# CH32V467WEU-R0.net
KiCad netlist of a schematic drawn in Altium Designer
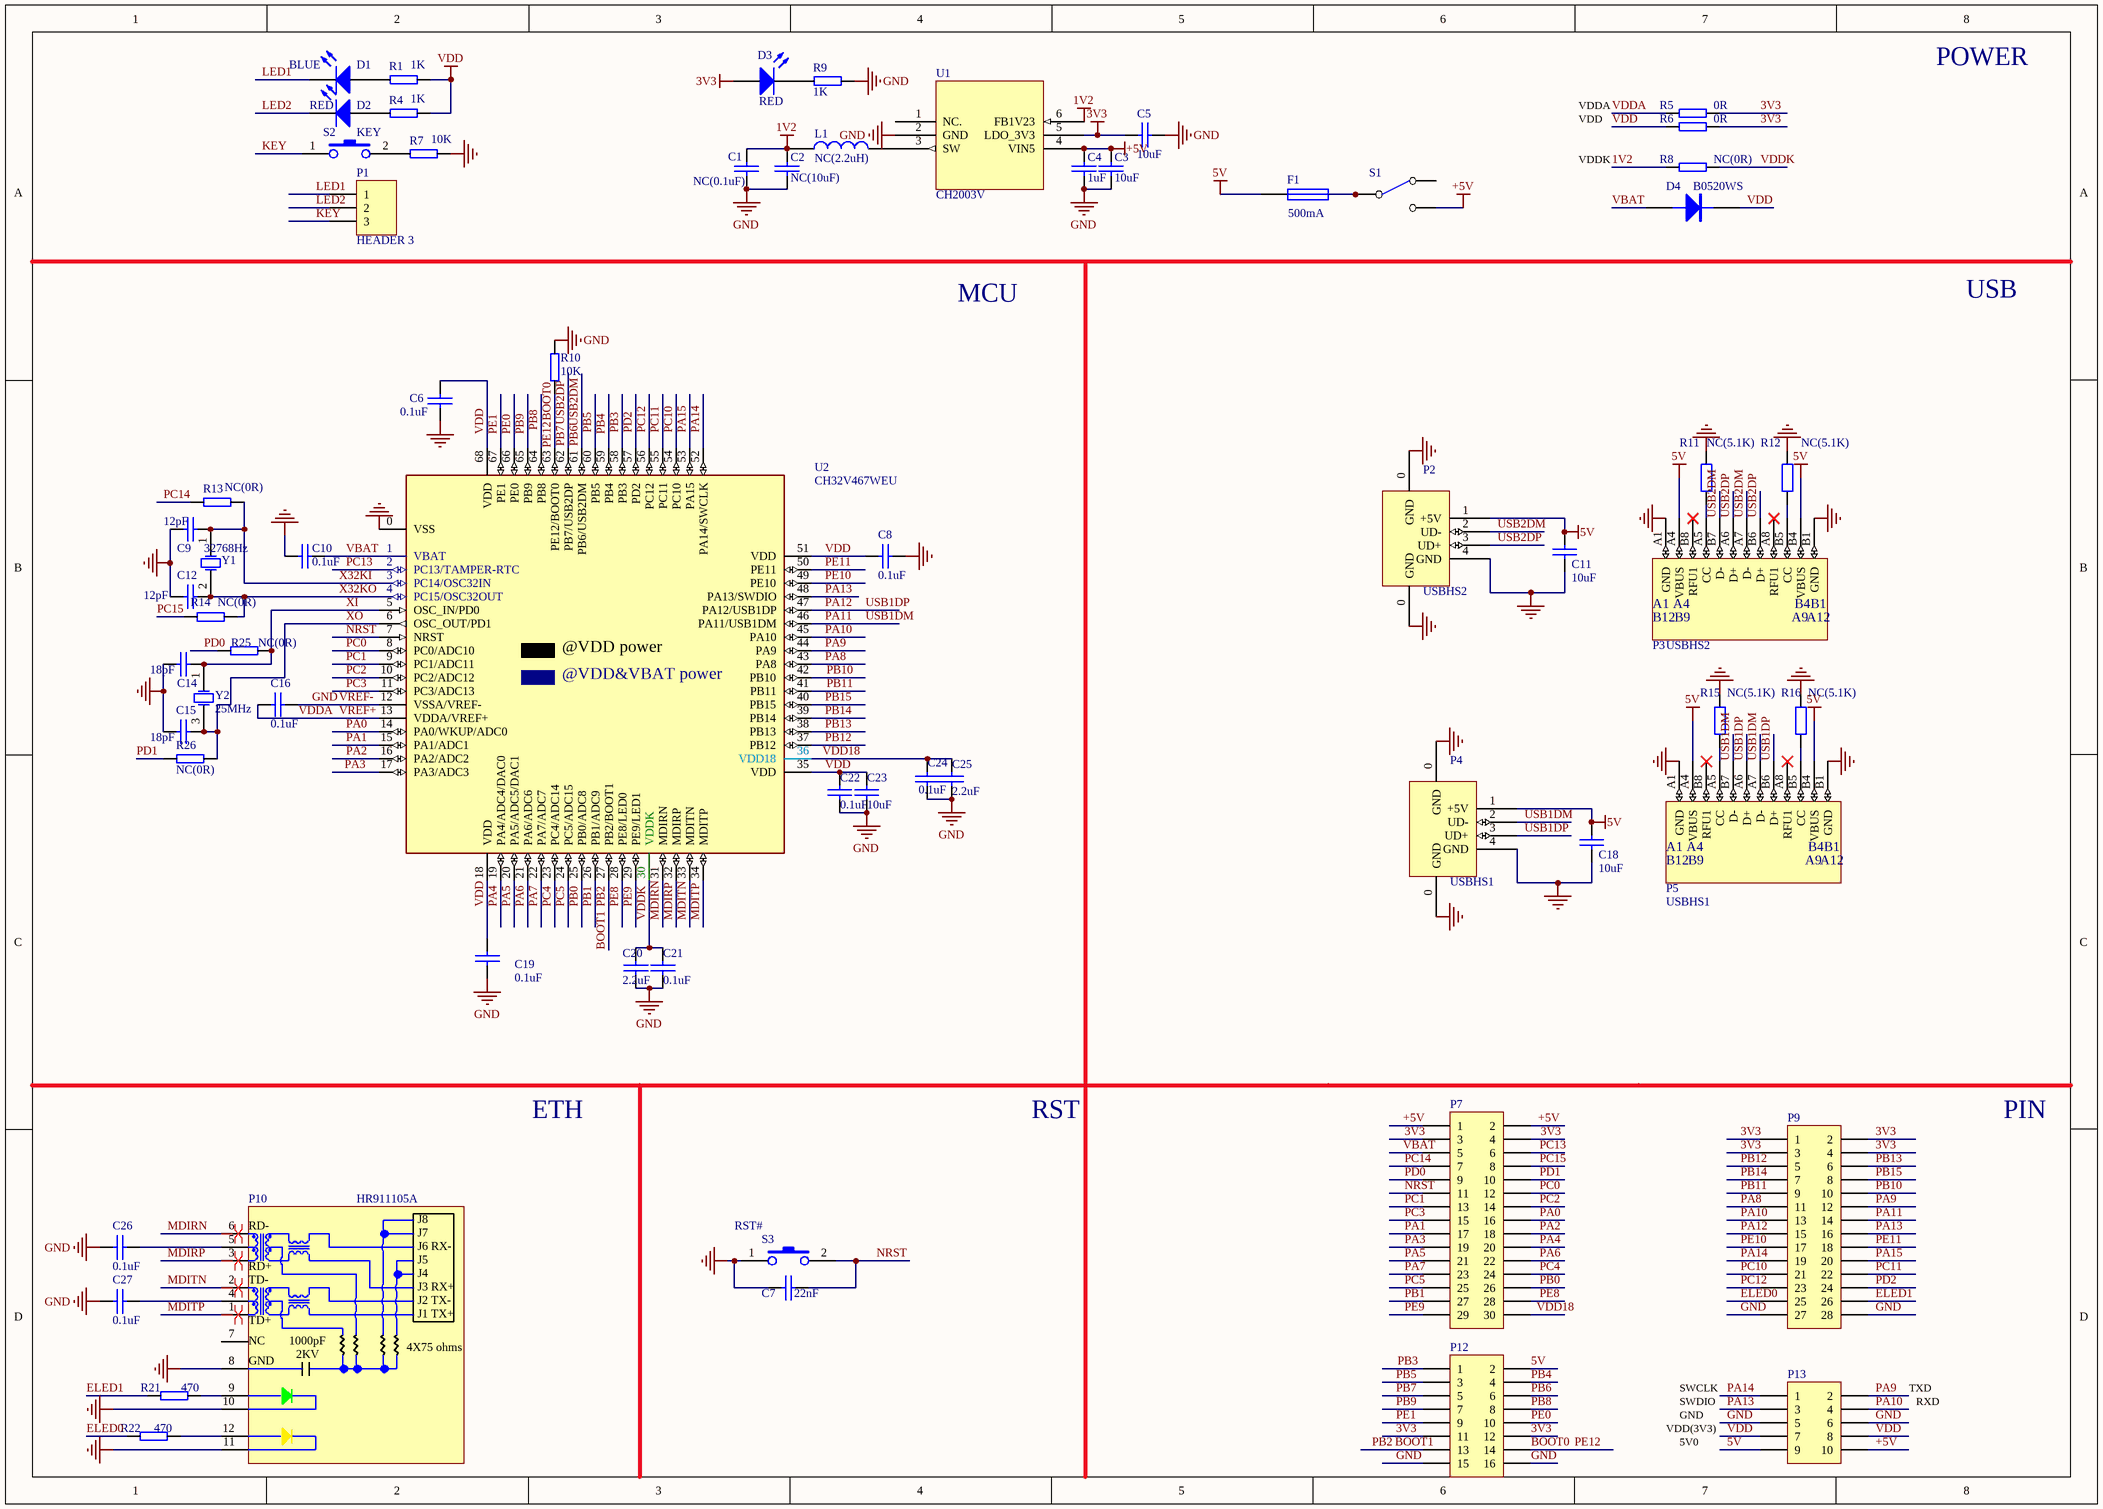
[diagram p0: CH32V467WEU-R0.SchDoc]

(export (version "E")
  (design (tool "Eeschema 10.0.6"))
  (components
    (comp (ref "C1")
      (value "NC(0.1uF)")
      (footprint "0402_C")
      (description "Capacitor")
      (libsource (lib "") (part "CAP_2"))
    )
    (comp (ref "C2")
      (value "NC(10uF)")
      (footprint "0603_C")
      (description "Capacitor")
      (libsource (lib "*") (part "CAP"))
    )
    (comp (ref "C3")
      (value "10uF")
      (footprint "0603_C")
      (description "Capacitor")
      (libsource (lib "*") (part "CAP"))
    )
    (comp (ref "C4")
      (value "1uF")
      (footprint "0402_C")
      (description "Capacitor")
      (libsource (lib "") (part "CAP_2"))
    )
    (comp (ref "C5")
      (value "10uF")
      (footprint "0603_C")
      (description "Capacitor")
      (libsource (lib "*") (part "CAP"))
    )
    (comp (ref "C6")
      (value "0.1uF")
      (footprint "0402_C")
      (description "Capacitor")
      (libsource (lib "*") (part "CAP"))
    )
    (comp (ref "C7")
      (value "22nF")
      (footprint "0402_C")
      (description "Capacitor")
      (libsource (lib "") (part "CAP_1"))
    )
    (comp (ref "C8")
      (value "0.1uF")
      (footprint "0402_C")
      (description "Capacitor")
      (libsource (lib "*") (part "CAP"))
    )
    (comp (ref "C9")
      (value "12pF")
      (footprint "0402_C")
      (description "Capacitor")
      (libsource (lib "*") (part "CAP"))
    )
    (comp (ref "C10")
      (value "0.1uF")
      (footprint "0402_C")
      (description "Capacitor")
      (libsource (lib "*") (part "CAP"))
    )
    (comp (ref "C11")
      (value "10uF")
      (footprint "0603_C")
      (description "Capacitor")
      (libsource (lib "") (part "CAP_1"))
    )
    (comp (ref "C12")
      (value "12pF")
      (footprint "0402_C")
      (description "Capacitor")
      (libsource (lib "*") (part "CAP"))
    )
    (comp (ref "C14")
      (value "18pF")
      (footprint "0402_C")
      (description "Capacitor")
      (libsource (lib "*") (part "CAP"))
    )
    (comp (ref "C15")
      (value "18pF")
      (footprint "0402_C")
      (description "Capacitor")
      (libsource (lib "*") (part "CAP"))
    )
    (comp (ref "C16")
      (value "0.1uF")
      (footprint "0402_C")
      (description "Capacitor")
      (libsource (lib "*") (part "CAP"))
    )
    (comp (ref "C18")
      (value "10uF")
      (footprint "0603_C")
      (description "Capacitor")
      (libsource (lib "") (part "CAP_1"))
    )
    (comp (ref "C19")
      (value "0.1uF")
      (footprint "0402_C")
      (description "Capacitor")
      (libsource (lib "*") (part "CAP"))
    )
    (comp (ref "C20")
      (value "2.2uF")
      (footprint "0402_C")
      (description "Capacitor")
      (libsource (lib "*") (part "CAP"))
    )
    (comp (ref "C21")
      (value "0.1uF")
      (footprint "0402_C")
      (description "Capacitor")
      (libsource (lib "*") (part "CAP"))
    )
    (comp (ref "C22")
      (value "0.1uF")
      (footprint "0402_C")
      (description "Capacitor")
      (libsource (lib "*") (part "CAP"))
    )
    (comp (ref "C23")
      (value "10uF")
      (footprint "0603_C")
      (description "Capacitor")
      (libsource (lib "*") (part "CAP"))
    )
    (comp (ref "C24")
      (value "0.1uF")
      (footprint "0402_C")
      (description "Capacitor")
      (libsource (lib "*") (part "CAP"))
    )
    (comp (ref "C25")
      (value "2.2uF")
      (footprint "0402_C")
      (description "Capacitor")
      (libsource (lib "*") (part "CAP"))
    )
    (comp (ref "C26")
      (value "0.1uF")
      (footprint "0402_C")
      (description "Capacitor")
      (libsource (lib "wch_sch_others") (part "CAP"))
    )
    (comp (ref "C27")
      (value "0.1uF")
      (footprint "0402_C")
      (description "Capacitor")
      (libsource (lib "wch_sch_others") (part "CAP"))
    )
    (comp (ref "D1")
      (value "BLUE")
      (footprint "0603+")
      (description "Typical INFRARED GaAs LED")
      (fields (field (name "PUBLISHER") "Altium Limited"))
      (libsource (lib "*") (part "LED0"))
    )
    (comp (ref "D2")
      (value "RED")
      (footprint "0603+")
      (description "Typical INFRARED GaAs LED")
      (fields (field (name "PUBLISHER") "Altium Limited"))
      (libsource (lib "*") (part "LED0"))
    )
    (comp (ref "D3")
      (value "RED")
      (footprint "0603+")
      (description "Typical INFRARED GaAs LED")
      (fields (field (name "PUBLISHER") "Altium Limited"))
      (libsource (lib "*") (part "LED0"))
    )
    (comp (ref "D4")
      (value "B0520WS")
      (footprint "SOD-323")
      (description "Diode")
      (libsource (lib "*") (part "DIODE"))
    )
    (comp (ref "F1")
      (value "500mA")
      (footprint "0603")
      (description "Fuse")
      (libsource (lib "wch_sch_others") (part "FUSE1"))
    )
    (comp (ref "L1") (value "NC(2.2uH)") (footprint "CD32") (libsource (lib "*") (part "INDUCTOR")))
    (comp (ref "P1")
      (value "HEADER 3")
      (footprint "SIP3-2.54MM")
      (description "Header, 3-Pin")
      (libsource (lib "wch_sch_others") (part "HEADER 3"))
    )
    (comp (ref "P2")
      (value "USBHS2")
      (footprint "USBAF")
      (description "USB Port")
      (libsource (lib "*") (part "USB"))
    )
    (comp (ref "P3")
      (value "USBHS2")
      (footprint "TYPE-C-Receptacle-2.0")
      (libsource (lib "*") (part "TYPE-C1"))
    )
    (comp (ref "P4")
      (value "USBHS1")
      (footprint "USBAF")
      (description "USB Port")
      (libsource (lib "*") (part "USB"))
    )
    (comp (ref "P5")
      (value "USBHS1")
      (footprint "TYPE-C-Receptacle-2.0")
      (libsource (lib "*") (part "TYPE-C1"))
    )
    (comp (ref "P7")
      (value "HEADER 15x2")
      (footprint "MYPCB:IDC30-2.54MM")
      (description "Header, 15-Pin, Dual row")
      (libsource (lib "wch_sch_others") (part "HEADER 15x2"))
    )
    (comp (ref "P9")
      (value "HEADER 14x2")
      (footprint "MYPCB:IDC28-2.54MM")
      (description "Header, 14-Pin, Dual row")
      (libsource (lib "wch_sch_others") (part "HEADER 14x2"))
    )
    (comp (ref "P10") (value "HR911105A") (footprint "HR911105A") (libsource (lib "*") (part "HR911105A")))
    (comp (ref "P12")
      (value "Ppin")
      (footprint "IDC16-2.54mm")
      (description "Header, 8-Pin, Dual row, Right Angle")
      (fields (field (name "PUBLISHER") "Altium Limited"))
      (libsource (lib "Miscellaneous Connectors") (part "Header 8X2H"))
    )
    (comp (ref "P13")
      (value "LINK")
      (footprint "IDC10-2.54mm")
      (description "Header, 5-Pin, Dual row, Right Angle")
      (fields (field (name "PUBLISHER") "Altium Limited"))
      (libsource (lib "Miscellaneous Connectors") (part "Header 5X2H"))
    )
    (comp (ref "R1") (value "1K") (footprint "0402") (libsource (lib "wch_sch_others") (part "RES")))
    (comp (ref "R4") (value "1K") (footprint "0402") (libsource (lib "wch_sch_others") (part "RES")))
    (comp (ref "R5") (value "0R") (footprint "0402") (libsource (lib "*") (part "R")))
    (comp (ref "R6") (value "0R") (footprint "0402") (libsource (lib "*") (part "R")))
    (comp (ref "R7") (value "10K") (footprint "0402") (libsource (lib "wch_sch_others") (part "RES")))
    (comp (ref "R8") (value "NC(0R)") (footprint "0402") (libsource (lib "*") (part "R")))
    (comp (ref "R9") (value "1K") (footprint "0402") (libsource (lib "wch_sch_others") (part "RES")))
    (comp (ref "R10") (value "10K") (footprint "0402") (libsource (lib "wch_sch_others") (part "RES")))
    (comp (ref "R11")
      (value "NC(5.1K)")
      (footprint "0402")
      (description "Resistor")
      (libsource (lib "Miscellaneous Devices") (part "Res2"))
    )
    (comp (ref "R12")
      (value "NC(5.1K)")
      (footprint "0402")
      (description "Resistor")
      (libsource (lib "Miscellaneous Devices") (part "Res2"))
    )
    (comp (ref "R13") (value "NC(0R)") (footprint "0402") (libsource (lib "wch_sch_others") (part "RES")))
    (comp (ref "R14") (value "NC(0R)") (footprint "0402") (libsource (lib "wch_sch_others") (part "RES")))
    (comp (ref "R15")
      (value "NC(5.1K)")
      (footprint "0402")
      (description "Resistor")
      (libsource (lib "Miscellaneous Devices") (part "Res2"))
    )
    (comp (ref "R16")
      (value "NC(5.1K)")
      (footprint "0402")
      (description "Resistor")
      (libsource (lib "Miscellaneous Devices") (part "Res2"))
    )
    (comp (ref "R21") (value "470") (footprint "0402") (libsource (lib "wch_sch_others") (part "RES")))
    (comp (ref "R22") (value "470") (footprint "0402") (libsource (lib "wch_sch_others") (part "RES")))
    (comp (ref "R25") (value "NC(0R)") (footprint "0402") (libsource (lib "wch_sch_others") (part "RES")))
    (comp (ref "R26") (value "NC(0R)") (footprint "0402") (libsource (lib "wch_sch_others") (part "RES")))
    (comp (ref "S1") (value "SW SPDT") (footprint "SW1") (libsource (lib "*") (part "SW SPDT")))
    (comp (ref "S2")
      (value "KEY")
      (footprint "SMD_6.1x3.65x2.5mm-KEY")
      (libsource (lib "wch_sch_others") (part "KEY1"))
    )
    (comp (ref "S3")
      (value "RST#")
      (footprint "SMD_6.1x3.65x2.5mm-KEY")
      (libsource (lib "wch_sch_others") (part "KEY1"))
    )
    (comp (ref "U1")
      (value "CH2003V")
      (footprint "SOT-23-6")
      (description "Step-Down DC-DC Converter, 5V input, 1.23V * 800mA output, with LDO 3.3V * 200mA")
      (libsource (lib "CHXXX") (part "CH2003V"))
    )
    (comp (ref "U2")
      (value "CH32V467WEU")
      (footprint "QFN68_8X8")
      (description "RISC-V FPU HD-MCU, 175MHz, USB_480M, 100M Ethernet & Phy, CAN, ADC, DAC, SRAM")
      (libsource (lib "CHXXX") (part "CH32V467WEU"))
    )
    (comp (ref "Y1")
      (value "32768Hz")
      (footprint "FC-135")
      (description "Crystal Oscillator")
      (fields (field (name "PUBLISHER") "Altium Limited"))
      (libsource (lib "") (part "XTAL_1"))
    )
    (comp (ref "Y2")
      (value "25MHz")
      (footprint "XT3225")
      (description "Crystal Oscillator")
      (fields (field (name "PUBLISHER") "Altium Limited"))
      (libsource (lib "*") (part "XTAL"))
    )
  )
  (nets
    (net (code "1") (name "+5V") (class "Default")
      (node (ref "C3") (pin "2") (pinfunction "2_2") (pintype "passive"))
      (node (ref "C4") (pin "2") (pinfunction "2_2") (pintype "passive"))
      (node (ref "P13") (pin "10") (pinfunction "10_10") (pintype "passive"))
      (node (ref "P7") (pin "1") (pinfunction "1_1") (pintype "passive"))
      (node (ref "P7") (pin "2") (pinfunction "2_2") (pintype "passive"))
      (node (ref "S1") (pin "2") (pinfunction "NC_2") (pintype "passive"))
      (node (ref "U1") (pin "4") (pinfunction "VIN5_4") (pintype "power_in"))
    )
    (net (code "3") (name "/BOOT0") (class "Default")
      (node (ref "P12") (pin "14") (pinfunction "14_14") (pintype "passive"))
      (node (ref "R10") (pin "2") (pintype "passive"))
      (node (ref "U2") (pin "63") (pinfunction "PE12/BOOT0_63") (pintype "bidirectional"))
    )
    (net (code "4") (name "/BOOT1") (class "Default")
      (node (ref "P12") (pin "13") (pinfunction "13_13") (pintype "passive"))
      (node (ref "U2") (pin "27") (pinfunction "PB2/BOOT1_27") (pintype "bidirectional"))
    )
    (net (code "5") (name "/ELED0") (class "Default")
      (node (ref "P9") (pin "25") (pinfunction "25_25") (pintype "passive"))
      (node (ref "R22") (pin "1") (pintype "passive"))
    )
    (net (code "6") (name "/ELED1") (class "Default")
      (node (ref "P9") (pin "26") (pinfunction "26_26") (pintype "passive"))
      (node (ref "R21") (pin "1") (pintype "passive"))
    )
    (net (code "7") (name "/KEY") (class "Default")
      (node (ref "P1") (pin "3") (pinfunction "3_3") (pintype "passive"))
      (node (ref "S2") (pin "1") (pinfunction "1_1") (pintype "passive"))
    )
    (net (code "8") (name "/LED1") (class "Default")
      (node (ref "D1") (pin "2") (pinfunction "K_2") (pintype "passive"))
      (node (ref "P1") (pin "1") (pinfunction "1_1") (pintype "passive"))
    )
    (net (code "9") (name "/LED2") (class "Default")
      (node (ref "D2") (pin "2") (pinfunction "K_2") (pintype "passive"))
      (node (ref "P1") (pin "2") (pinfunction "2_2") (pintype "passive"))
    )
    (net (code "10") (name "/MDIRN") (class "Default")
      (node (ref "P10") (pin "6") (pintype "passive"))
      (node (ref "U2") (pin "31") (pinfunction "MDIRN_31") (pintype "bidirectional"))
    )
    (net (code "11") (name "/MDIRP") (class "Default")
      (node (ref "P10") (pin "3") (pintype "passive"))
      (node (ref "U2") (pin "32") (pinfunction "MDIRP_32") (pintype "bidirectional"))
    )
    (net (code "12") (name "/MDITN") (class "Default")
      (node (ref "P10") (pin "2") (pintype "passive"))
      (node (ref "U2") (pin "33") (pinfunction "MDITN_33") (pintype "bidirectional"))
    )
    (net (code "13") (name "/MDITP") (class "Default")
      (node (ref "P10") (pin "1") (pintype "passive"))
      (node (ref "U2") (pin "34") (pinfunction "MDITP_34") (pintype "bidirectional"))
    )
    (net (code "14") (name "/NRST") (class "Default")
      (node (ref "C7") (pin "2") (pinfunction "2_2") (pintype "passive"))
      (node (ref "P7") (pin "11") (pinfunction "11_11") (pintype "passive"))
      (node (ref "S3") (pin "2") (pinfunction "2_2") (pintype "passive"))
      (node (ref "U2") (pin "7") (pinfunction "NRST_7") (pintype "input"))
    )
    (net (code "15") (name "/PA0") (class "Default")
      (node (ref "P7") (pin "16") (pinfunction "16_16") (pintype "passive"))
      (node (ref "U2") (pin "14") (pinfunction "PA0/WKUP/ADC0_14") (pintype "bidirectional"))
    )
    (net (code "16") (name "/PA1") (class "Default")
      (node (ref "P7") (pin "17") (pinfunction "17_17") (pintype "passive"))
      (node (ref "U2") (pin "15") (pinfunction "PA1/ADC1_15") (pintype "bidirectional"))
    )
    (net (code "17") (name "/PA2") (class "Default")
      (node (ref "P7") (pin "18") (pinfunction "18_18") (pintype "passive"))
      (node (ref "U2") (pin "16") (pinfunction "PA2/ADC2_16") (pintype "bidirectional"))
    )
    (net (code "18") (name "/PA3") (class "Default")
      (node (ref "P7") (pin "19") (pinfunction "19_19") (pintype "passive"))
      (node (ref "U2") (pin "17") (pinfunction "PA3/ADC3_17") (pintype "bidirectional"))
    )
    (net (code "19") (name "/PA4") (class "Default")
      (node (ref "P7") (pin "20") (pinfunction "20_20") (pintype "passive"))
      (node (ref "U2") (pin "19") (pinfunction "PA4/ADC4/DAC0_19") (pintype "bidirectional"))
    )
    (net (code "20") (name "/PA5") (class "Default")
      (node (ref "P7") (pin "21") (pinfunction "21_21") (pintype "passive"))
      (node (ref "U2") (pin "20") (pinfunction "PA5/ADC5/DAC1_20") (pintype "bidirectional"))
    )
    (net (code "21") (name "/PA6") (class "Default")
      (node (ref "P7") (pin "22") (pinfunction "22_22") (pintype "passive"))
      (node (ref "U2") (pin "21") (pinfunction "PA6/ADC6_21") (pintype "bidirectional"))
    )
    (net (code "22") (name "/PA7") (class "Default")
      (node (ref "P7") (pin "23") (pinfunction "23_23") (pintype "passive"))
      (node (ref "U2") (pin "22") (pinfunction "PA7/ADC7_22") (pintype "bidirectional"))
    )
    (net (code "23") (name "/PA8") (class "Default")
      (node (ref "P9") (pin "11") (pinfunction "11_11") (pintype "passive"))
      (node (ref "U2") (pin "43") (pinfunction "PA8_43") (pintype "bidirectional"))
    )
    (net (code "24") (name "/PA9") (class "Default")
      (node (ref "P13") (pin "2") (pinfunction "2_2") (pintype "passive"))
      (node (ref "P9") (pin "12") (pinfunction "12_12") (pintype "passive"))
      (node (ref "U2") (pin "44") (pinfunction "PA9_44") (pintype "bidirectional"))
    )
    (net (code "25") (name "/PA10") (class "Default")
      (node (ref "P13") (pin "4") (pinfunction "4_4") (pintype "passive"))
      (node (ref "P9") (pin "13") (pinfunction "13_13") (pintype "passive"))
      (node (ref "U2") (pin "45") (pinfunction "PA10_45") (pintype "bidirectional"))
    )
    (net (code "26") (name "/PA11") (class "Default")
      (node (ref "P4") (pin "2") (pinfunction "UD-_2") (pintype "bidirectional"))
      (node (ref "P5") (pin "A7") (pinfunction "D-_A7") (pintype "bidirectional"))
      (node (ref "P5") (pin "B7") (pinfunction "D-_B7") (pintype "bidirectional"))
      (node (ref "P9") (pin "14") (pinfunction "14_14") (pintype "passive"))
      (node (ref "U2") (pin "46") (pinfunction "PA11/USB1DM_46") (pintype "bidirectional"))
    )
    (net (code "27") (name "/PA12") (class "Default")
      (node (ref "P4") (pin "3") (pinfunction "UD+_3") (pintype "bidirectional"))
      (node (ref "P5") (pin "A6") (pinfunction "D+_A6") (pintype "bidirectional"))
      (node (ref "P5") (pin "B6") (pinfunction "D+_B6") (pintype "bidirectional"))
      (node (ref "P9") (pin "15") (pinfunction "15_15") (pintype "passive"))
      (node (ref "U2") (pin "47") (pinfunction "PA12/USB1DP_47") (pintype "bidirectional"))
    )
    (net (code "28") (name "/PA13") (class "Default")
      (node (ref "P13") (pin "3") (pinfunction "3_3") (pintype "passive"))
      (node (ref "P9") (pin "16") (pinfunction "16_16") (pintype "passive"))
      (node (ref "U2") (pin "48") (pinfunction "PA13/SWDIO_48") (pintype "bidirectional"))
    )
    (net (code "29") (name "/PA14") (class "Default")
      (node (ref "P13") (pin "1") (pinfunction "1_1") (pintype "passive"))
      (node (ref "P9") (pin "19") (pinfunction "19_19") (pintype "passive"))
      (node (ref "U2") (pin "52") (pinfunction "PA14/SWCLK_52") (pintype "bidirectional"))
    )
    (net (code "30") (name "/PA15") (class "Default")
      (node (ref "P9") (pin "20") (pinfunction "20_20") (pintype "passive"))
      (node (ref "U2") (pin "53") (pinfunction "PA15_53") (pintype "bidirectional"))
    )
    (net (code "31") (name "/PB0") (class "Default")
      (node (ref "P7") (pin "26") (pinfunction "26_26") (pintype "passive"))
      (node (ref "U2") (pin "25") (pinfunction "PB0/ADC8_25") (pintype "bidirectional"))
    )
    (net (code "32") (name "/PB1") (class "Default")
      (node (ref "P7") (pin "27") (pinfunction "27_27") (pintype "passive"))
      (node (ref "U2") (pin "26") (pinfunction "PB1/ADC9_26") (pintype "bidirectional"))
    )
    (net (code "33") (name "/PB3") (class "Default")
      (node (ref "P12") (pin "1") (pinfunction "1_1") (pintype "passive"))
      (node (ref "U2") (pin "58") (pinfunction "PB3_58") (pintype "bidirectional"))
    )
    (net (code "34") (name "/PB4") (class "Default")
      (node (ref "P12") (pin "4") (pinfunction "4_4") (pintype "passive"))
      (node (ref "U2") (pin "59") (pinfunction "PB4_59") (pintype "bidirectional"))
    )
    (net (code "35") (name "/PB5") (class "Default")
      (node (ref "P12") (pin "3") (pinfunction "3_3") (pintype "passive"))
      (node (ref "U2") (pin "60") (pinfunction "PB5_60") (pintype "bidirectional"))
    )
    (net (code "36") (name "/PB6") (class "Default")
      (node (ref "P12") (pin "6") (pinfunction "6_6") (pintype "passive"))
      (node (ref "P2") (pin "2") (pinfunction "UD-_2") (pintype "bidirectional"))
      (node (ref "P3") (pin "A7") (pinfunction "D-_A7") (pintype "bidirectional"))
      (node (ref "P3") (pin "B7") (pinfunction "D-_B7") (pintype "bidirectional"))
      (node (ref "U2") (pin "61") (pinfunction "PB6/USB2DM_61") (pintype "bidirectional"))
    )
    (net (code "37") (name "/PB7") (class "Default")
      (node (ref "P12") (pin "5") (pinfunction "5_5") (pintype "passive"))
      (node (ref "P2") (pin "3") (pinfunction "UD+_3") (pintype "bidirectional"))
      (node (ref "P3") (pin "A6") (pinfunction "D+_A6") (pintype "bidirectional"))
      (node (ref "P3") (pin "B6") (pinfunction "D+_B6") (pintype "bidirectional"))
      (node (ref "U2") (pin "62") (pinfunction "PB7/USB2DP_62") (pintype "bidirectional"))
    )
    (net (code "38") (name "/PB8") (class "Default")
      (node (ref "P12") (pin "8") (pinfunction "8_8") (pintype "passive"))
      (node (ref "U2") (pin "64") (pinfunction "PB8_64") (pintype "bidirectional"))
    )
    (net (code "39") (name "/PB9") (class "Default")
      (node (ref "P12") (pin "7") (pinfunction "7_7") (pintype "passive"))
      (node (ref "U2") (pin "65") (pinfunction "PB9_65") (pintype "bidirectional"))
    )
    (net (code "40") (name "/PB10") (class "Default")
      (node (ref "P9") (pin "10") (pinfunction "10_10") (pintype "passive"))
      (node (ref "U2") (pin "42") (pinfunction "PB10_42") (pintype "bidirectional"))
    )
    (net (code "41") (name "/PB11") (class "Default")
      (node (ref "P9") (pin "9") (pinfunction "9_9") (pintype "passive"))
      (node (ref "U2") (pin "41") (pinfunction "PB11_41") (pintype "bidirectional"))
    )
    (net (code "42") (name "/PB12") (class "Default")
      (node (ref "P9") (pin "5") (pinfunction "5_5") (pintype "passive"))
      (node (ref "U2") (pin "37") (pinfunction "PB12_37") (pintype "bidirectional"))
    )
    (net (code "43") (name "/PB13") (class "Default")
      (node (ref "P9") (pin "6") (pinfunction "6_6") (pintype "passive"))
      (node (ref "U2") (pin "38") (pinfunction "PB13_38") (pintype "bidirectional"))
    )
    (net (code "44") (name "/PB14") (class "Default")
      (node (ref "P9") (pin "7") (pinfunction "7_7") (pintype "passive"))
      (node (ref "U2") (pin "39") (pinfunction "PB14_39") (pintype "bidirectional"))
    )
    (net (code "45") (name "/PB15") (class "Default")
      (node (ref "P9") (pin "8") (pinfunction "8_8") (pintype "passive"))
      (node (ref "U2") (pin "40") (pinfunction "PB15_40") (pintype "bidirectional"))
    )
    (net (code "46") (name "/PC0") (class "Default")
      (node (ref "P7") (pin "12") (pinfunction "12_12") (pintype "passive"))
      (node (ref "U2") (pin "8") (pinfunction "PC0/ADC10_8") (pintype "bidirectional"))
    )
    (net (code "47") (name "/PC1") (class "Default")
      (node (ref "P7") (pin "13") (pinfunction "13_13") (pintype "passive"))
      (node (ref "U2") (pin "9") (pinfunction "PC1/ADC11_9") (pintype "bidirectional"))
    )
    (net (code "48") (name "/PC2") (class "Default")
      (node (ref "P7") (pin "14") (pinfunction "14_14") (pintype "passive"))
      (node (ref "U2") (pin "10") (pinfunction "PC2/ADC12_10") (pintype "bidirectional"))
    )
    (net (code "49") (name "/PC3") (class "Default")
      (node (ref "P7") (pin "15") (pinfunction "15_15") (pintype "passive"))
      (node (ref "U2") (pin "11") (pinfunction "PC3/ADC13_11") (pintype "bidirectional"))
    )
    (net (code "50") (name "/PC4") (class "Default")
      (node (ref "P7") (pin "24") (pinfunction "24_24") (pintype "passive"))
      (node (ref "U2") (pin "23") (pinfunction "PC4/ADC14_23") (pintype "bidirectional"))
    )
    (net (code "51") (name "/PC5") (class "Default")
      (node (ref "P7") (pin "25") (pinfunction "25_25") (pintype "passive"))
      (node (ref "U2") (pin "24") (pinfunction "PC5/ADC15_24") (pintype "bidirectional"))
    )
    (net (code "52") (name "/PC10") (class "Default")
      (node (ref "P9") (pin "21") (pinfunction "21_21") (pintype "passive"))
      (node (ref "U2") (pin "54") (pinfunction "PC10_54") (pintype "bidirectional"))
    )
    (net (code "53") (name "/PC11") (class "Default")
      (node (ref "P9") (pin "22") (pinfunction "22_22") (pintype "passive"))
      (node (ref "U2") (pin "55") (pinfunction "PC11_55") (pintype "bidirectional"))
    )
    (net (code "54") (name "/PC12") (class "Default")
      (node (ref "P9") (pin "23") (pinfunction "23_23") (pintype "passive"))
      (node (ref "U2") (pin "56") (pinfunction "PC12_56") (pintype "bidirectional"))
    )
    (net (code "55") (name "/PC13") (class "Default")
      (node (ref "P7") (pin "6") (pinfunction "6_6") (pintype "passive"))
      (node (ref "U2") (pin "2") (pinfunction "PC13/TAMPER-RTC_2") (pintype "bidirectional"))
    )
    (net (code "56") (name "/PC14") (class "Default")
      (node (ref "P7") (pin "7") (pinfunction "7_7") (pintype "passive"))
      (node (ref "R13") (pin "1") (pintype "passive"))
    )
    (net (code "57") (name "/PC15") (class "Default")
      (node (ref "P7") (pin "8") (pinfunction "8_8") (pintype "passive"))
      (node (ref "R14") (pin "1") (pintype "passive"))
    )
    (net (code "58") (name "/PD0") (class "Default")
      (node (ref "P7") (pin "9") (pinfunction "9_9") (pintype "passive"))
      (node (ref "R25") (pin "1") (pintype "passive"))
    )
    (net (code "59") (name "/PD1") (class "Default")
      (node (ref "P7") (pin "10") (pinfunction "10_10") (pintype "passive"))
      (node (ref "R26") (pin "2") (pintype "passive"))
    )
    (net (code "60") (name "/PD2") (class "Default")
      (node (ref "P9") (pin "24") (pinfunction "24_24") (pintype "passive"))
      (node (ref "U2") (pin "57") (pinfunction "PD2_57") (pintype "bidirectional"))
    )
    (net (code "61") (name "/PE0") (class "Default")
      (node (ref "P12") (pin "10") (pinfunction "10_10") (pintype "passive"))
      (node (ref "U2") (pin "66") (pinfunction "PE0_66") (pintype "bidirectional"))
    )
    (net (code "62") (name "/PE1") (class "Default")
      (node (ref "P12") (pin "9") (pinfunction "9_9") (pintype "passive"))
      (node (ref "U2") (pin "67") (pinfunction "PE1_67") (pintype "bidirectional"))
    )
    (net (code "63") (name "/PE8") (class "Default")
      (node (ref "P7") (pin "28") (pinfunction "28_28") (pintype "passive"))
      (node (ref "U2") (pin "28") (pinfunction "PE8/LED0_28") (pintype "bidirectional"))
    )
    (net (code "64") (name "/PE9") (class "Default")
      (node (ref "P7") (pin "29") (pinfunction "29_29") (pintype "passive"))
      (node (ref "U2") (pin "29") (pinfunction "PE9/LED1_29") (pintype "bidirectional"))
    )
    (net (code "65") (name "/PE10") (class "Default")
      (node (ref "P9") (pin "17") (pinfunction "17_17") (pintype "passive"))
      (node (ref "U2") (pin "49") (pinfunction "PE10_49") (pintype "bidirectional"))
    )
    (net (code "66") (name "/PE11") (class "Default")
      (node (ref "P9") (pin "18") (pinfunction "18_18") (pintype "passive"))
      (node (ref "U2") (pin "50") (pinfunction "PE11_50") (pintype "bidirectional"))
    )
    (net (code "67") (name "/VBAT") (class "Default")
      (node (ref "C10") (pin "2") (pinfunction "2_2") (pintype "passive"))
      (node (ref "D4") (pin "1") (pinfunction "A_1") (pintype "passive"))
      (node (ref "P7") (pin "5") (pinfunction "5_5") (pintype "passive"))
      (node (ref "U2") (pin "1") (pinfunction "VBAT_1") (pintype "power_in"))
    )
    (net (code "68") (name "/VDD18") (class "Default")
      (node (ref "C24") (pin "2") (pinfunction "2_2") (pintype "passive"))
      (node (ref "C25") (pin "2") (pinfunction "2_2") (pintype "passive"))
      (node (ref "P7") (pin "30") (pinfunction "30_30") (pintype "passive"))
      (node (ref "U2") (pin "36") (pinfunction "VDD18_36") (pintype "power_in"))
    )
    (net (code "69") (name "/VDDA") (class "Default")
      (node (ref "C16") (pin "1") (pinfunction "1_1") (pintype "passive"))
      (node (ref "R5") (pin "2") (pinfunction "2_2") (pintype "passive"))
      (node (ref "U2") (pin "13") (pinfunction "VDDA/VREF+_13") (pintype "power_in"))
    )
    (net (code "70") (name "/VDDK") (class "Default")
      (node (ref "C20") (pin "2") (pinfunction "2_2") (pintype "passive"))
      (node (ref "C21") (pin "2") (pinfunction "2_2") (pintype "passive"))
      (node (ref "R8") (pin "1") (pinfunction "1_1") (pintype "passive"))
      (node (ref "U2") (pin "30") (pinfunction "VDDK_30") (pintype "power_in"))
    )
    (net (code "71") (name "/X32KI") (class "Default")
      (node (ref "C9") (pin "2") (pinfunction "2_2") (pintype "passive"))
      (node (ref "R13") (pin "2") (pintype "passive"))
      (node (ref "U2") (pin "3") (pinfunction "PC14/OSC32IN_3") (pintype "bidirectional"))
      (node (ref "Y1") (pin "1") (pinfunction "OSC1_1") (pintype "passive"))
    )
    (net (code "72") (name "/X32KO") (class "Default")
      (node (ref "C12") (pin "2") (pinfunction "2_2") (pintype "passive"))
      (node (ref "R14") (pin "2") (pintype "passive"))
      (node (ref "U2") (pin "4") (pinfunction "PC15/OSC32OUT_4") (pintype "bidirectional"))
      (node (ref "Y1") (pin "2") (pinfunction "OSC2_2") (pintype "passive"))
    )
    (net (code "73") (name "/XI") (class "Default")
      (node (ref "C14") (pin "2") (pinfunction "2_2") (pintype "passive"))
      (node (ref "R25") (pin "2") (pintype "passive"))
      (node (ref "U2") (pin "5") (pinfunction "OSC_IN/PD0_5") (pintype "input"))
      (node (ref "Y2") (pin "1") (pinfunction "OSC1_1") (pintype "passive"))
    )
    (net (code "74") (name "/XO") (class "Default")
      (node (ref "C15") (pin "2") (pinfunction "2_2") (pintype "passive"))
      (node (ref "R26") (pin "1") (pintype "passive"))
      (node (ref "U2") (pin "6") (pinfunction "OSC_OUT/PD1_6") (pintype "output"))
      (node (ref "Y2") (pin "3") (pinfunction "OSC2_3") (pintype "passive"))
    )
    (net (code "75") (name "1V2") (class "Default")
      (node (ref "C1") (pin "2") (pinfunction "2_2") (pintype "passive"))
      (node (ref "C2") (pin "2") (pinfunction "2_2") (pintype "passive"))
      (node (ref "L1") (pin "2") (pinfunction "2_2") (pintype "passive"))
      (node (ref "R8") (pin "2") (pinfunction "2_2") (pintype "passive"))
      (node (ref "U1") (pin "6") (pinfunction "FB1V23_6") (pintype "input"))
    )
    (net (code "76") (name "3V3") (class "Default")
      (node (ref "C5") (pin "2") (pinfunction "2_2") (pintype "passive"))
      (node (ref "D3") (pin "1") (pinfunction "A_1") (pintype "passive"))
      (node (ref "P12") (pin "11") (pinfunction "11_11") (pintype "passive"))
      (node (ref "P12") (pin "12") (pinfunction "12_12") (pintype "passive"))
      (node (ref "P7") (pin "3") (pinfunction "3_3") (pintype "passive"))
      (node (ref "P7") (pin "4") (pinfunction "4_4") (pintype "passive"))
      (node (ref "P9") (pin "1") (pinfunction "1_1") (pintype "passive"))
      (node (ref "P9") (pin "2") (pinfunction "2_2") (pintype "passive"))
      (node (ref "P9") (pin "3") (pinfunction "3_3") (pintype "passive"))
      (node (ref "P9") (pin "4") (pinfunction "4_4") (pintype "passive"))
      (node (ref "R5") (pin "1") (pinfunction "1_1") (pintype "passive"))
      (node (ref "R6") (pin "1") (pinfunction "1_1") (pintype "passive"))
      (node (ref "U1") (pin "5") (pinfunction "LDO_3V3_5") (pintype "power_in"))
    )
    (net (code "77") (name "5V") (class "Default")
      (node (ref "C11") (pin "1") (pinfunction "1_1") (pintype "passive"))
      (node (ref "C18") (pin "1") (pinfunction "1_1") (pintype "passive"))
      (node (ref "F1") (pin "1") (pinfunction "1_1") (pintype "passive"))
      (node (ref "P12") (pin "2") (pinfunction "2_2") (pintype "passive"))
      (node (ref "P13") (pin "9") (pinfunction "9_9") (pintype "passive"))
      (node (ref "P2") (pin "1") (pinfunction "+5V_1") (pintype "power_in"))
      (node (ref "P3") (pin "A4") (pinfunction "VBUS_A4") (pintype "bidirectional"))
      (node (ref "P3") (pin "B4") (pinfunction "VBUS_B4") (pintype "bidirectional"))
      (node (ref "P4") (pin "1") (pinfunction "+5V_1") (pintype "power_in"))
      (node (ref "P5") (pin "A4") (pinfunction "VBUS_A4") (pintype "bidirectional"))
      (node (ref "P5") (pin "B4") (pinfunction "VBUS_B4") (pintype "bidirectional"))
    )
    (net (code "78") (name "GND") (class "Default")
      (node (ref "C1") (pin "1") (pinfunction "1_1") (pintype "passive"))
      (node (ref "C10") (pin "1") (pinfunction "1_1") (pintype "passive"))
      (node (ref "C11") (pin "2") (pinfunction "2_2") (pintype "passive"))
      (node (ref "C12") (pin "1") (pinfunction "1_1") (pintype "passive"))
      (node (ref "C14") (pin "1") (pinfunction "1_1") (pintype "passive"))
      (node (ref "C15") (pin "1") (pinfunction "1_1") (pintype "passive"))
      (node (ref "C16") (pin "2") (pinfunction "2_2") (pintype "passive"))
      (node (ref "C18") (pin "2") (pinfunction "2_2") (pintype "passive"))
      (node (ref "C19") (pin "1") (pinfunction "1_1") (pintype "passive"))
      (node (ref "C2") (pin "1") (pinfunction "1_1") (pintype "passive"))
      (node (ref "C20") (pin "1") (pinfunction "1_1") (pintype "passive"))
      (node (ref "C21") (pin "1") (pinfunction "1_1") (pintype "passive"))
      (node (ref "C22") (pin "1") (pinfunction "1_1") (pintype "passive"))
      (node (ref "C23") (pin "1") (pinfunction "1_1") (pintype "passive"))
      (node (ref "C24") (pin "1") (pinfunction "1_1") (pintype "passive"))
      (node (ref "C25") (pin "1") (pinfunction "1_1") (pintype "passive"))
      (node (ref "C26") (pin "1") (pinfunction "1_1") (pintype "passive"))
      (node (ref "C27") (pin "1") (pinfunction "1_1") (pintype "passive"))
      (node (ref "C3") (pin "1") (pinfunction "1_1") (pintype "passive"))
      (node (ref "C4") (pin "1") (pinfunction "1_1") (pintype "passive"))
      (node (ref "C5") (pin "1") (pinfunction "1_1") (pintype "passive"))
      (node (ref "C6") (pin "1") (pinfunction "1_1") (pintype "passive"))
      (node (ref "C7") (pin "1") (pinfunction "1_1") (pintype "passive"))
      (node (ref "C8") (pin "2") (pinfunction "2_2") (pintype "passive"))
      (node (ref "C9") (pin "1") (pinfunction "1_1") (pintype "passive"))
      (node (ref "P10") (pin "10") (pintype "passive"))
      (node (ref "P10") (pin "11") (pintype "passive"))
      (node (ref "P10") (pin "8") (pintype "passive"))
      (node (ref "P12") (pin "15") (pinfunction "15_15") (pintype "passive"))
      (node (ref "P12") (pin "16") (pinfunction "16_16") (pintype "passive"))
      (node (ref "P13") (pin "5") (pinfunction "5_5") (pintype "passive"))
      (node (ref "P13") (pin "6") (pinfunction "6_6") (pintype "passive"))
      (node (ref "P2") (pin "0") (pinfunction "GND_0") (pintype "power_in"))
      (node (ref "P2") (pin "4") (pinfunction "GND_4") (pintype "power_in"))
      (node (ref "P3") (pin "A1") (pinfunction "GND_A1") (pintype "bidirectional"))
      (node (ref "P3") (pin "B1") (pinfunction "GND_B1") (pintype "bidirectional"))
      (node (ref "P4") (pin "0") (pinfunction "GND_0") (pintype "power_in"))
      (node (ref "P4") (pin "4") (pinfunction "GND_4") (pintype "power_in"))
      (node (ref "P5") (pin "A1") (pinfunction "GND_A1") (pintype "bidirectional"))
      (node (ref "P5") (pin "B1") (pinfunction "GND_B1") (pintype "bidirectional"))
      (node (ref "P9") (pin "27") (pinfunction "27_27") (pintype "passive"))
      (node (ref "P9") (pin "28") (pinfunction "28_28") (pintype "passive"))
      (node (ref "R10") (pin "1") (pintype "passive"))
      (node (ref "R11") (pin "2") (pinfunction "2_2") (pintype "passive"))
      (node (ref "R12") (pin "2") (pinfunction "2_2") (pintype "passive"))
      (node (ref "R15") (pin "2") (pinfunction "2_2") (pintype "passive"))
      (node (ref "R16") (pin "2") (pinfunction "2_2") (pintype "passive"))
      (node (ref "R7") (pin "1") (pintype "passive"))
      (node (ref "R9") (pin "2") (pintype "passive"))
      (node (ref "S3") (pin "1") (pinfunction "1_1") (pintype "passive"))
      (node (ref "U1") (pin "2") (pinfunction "GND_2") (pintype "power_in"))
      (node (ref "U2") (pin "0") (pinfunction "VSS_0") (pintype "power_in"))
      (node (ref "U2") (pin "12") (pinfunction "VSSA/VREF-_12") (pintype "power_in"))
    )
    (net (code "79") (name "Net-(C26-Pad2)") (class "Default")
      (node (ref "C26") (pin "2") (pinfunction "2_2") (pintype "passive"))
      (node (ref "P10") (pin "5") (pintype "passive"))
    )
    (net (code "80") (name "Net-(C27-Pad2)") (class "Default")
      (node (ref "C27") (pin "2") (pinfunction "2_2") (pintype "passive"))
      (node (ref "P10") (pin "4") (pintype "passive"))
    )
    (net (code "81") (name "Net-(D1-A)") (class "Default")
      (node (ref "D1") (pin "1") (pinfunction "A_1") (pintype "passive"))
      (node (ref "R1") (pin "2") (pintype "passive"))
    )
    (net (code "82") (name "Net-(D2-A)") (class "Default")
      (node (ref "D2") (pin "1") (pinfunction "A_1") (pintype "passive"))
      (node (ref "R4") (pin "2") (pintype "passive"))
    )
    (net (code "83") (name "Net-(D3-K)") (class "Default")
      (node (ref "D3") (pin "2") (pinfunction "K_2") (pintype "passive"))
      (node (ref "R9") (pin "1") (pintype "passive"))
    )
    (net (code "84") (name "Net-(P3-CC-PadA5)") (class "Default")
      (node (ref "P3") (pin "A5") (pinfunction "CC_A5") (pintype "bidirectional"))
      (node (ref "R11") (pin "1") (pinfunction "1_1") (pintype "passive"))
    )
    (net (code "85") (name "Net-(P3-CC-PadB5)") (class "Default")
      (node (ref "P3") (pin "B5") (pinfunction "CC_B5") (pintype "bidirectional"))
      (node (ref "R12") (pin "1") (pinfunction "1_1") (pintype "passive"))
    )
    (net (code "86") (name "Net-(P5-CC-PadA5)") (class "Default")
      (node (ref "P5") (pin "A5") (pinfunction "CC_A5") (pintype "bidirectional"))
      (node (ref "R15") (pin "1") (pinfunction "1_1") (pintype "passive"))
    )
    (net (code "87") (name "Net-(P5-CC-PadB5)") (class "Default")
      (node (ref "P5") (pin "B5") (pinfunction "CC_B5") (pintype "bidirectional"))
      (node (ref "R16") (pin "1") (pinfunction "1_1") (pintype "passive"))
    )
    (net (code "88") (name "Net-(P10-Pad9)") (class "Default")
      (node (ref "P10") (pin "9") (pintype "passive"))
      (node (ref "R21") (pin "2") (pintype "passive"))
    )
    (net (code "89") (name "Net-(P10-Pad12)") (class "Default")
      (node (ref "P10") (pin "12") (pintype "passive"))
      (node (ref "R22") (pin "2") (pintype "passive"))
    )
    (net (code "90") (name "Net-(R7-Pad2)") (class "Default")
      (node (ref "R7") (pin "2") (pintype "passive"))
      (node (ref "S2") (pin "2") (pinfunction "2_2") (pintype "passive"))
    )
    (net (code "91") (name "Net-(S1-COMMON)") (class "Default")
      (node (ref "F1") (pin "2") (pinfunction "2_2") (pintype "passive"))
      (node (ref "S1") (pin "1") (pinfunction "COMMON_1") (pintype "passive"))
    )
    (net (code "92") (name "Net-(U1-SW)") (class "Default")
      (node (ref "L1") (pin "1") (pinfunction "1_1") (pintype "passive"))
      (node (ref "U1") (pin "3") (pinfunction "SW_3") (pintype "output"))
    )
    (net (code "93") (name "VDD") (class "Default")
      (node (ref "C19") (pin "2") (pinfunction "2_2") (pintype "passive"))
      (node (ref "C22") (pin "2") (pinfunction "2_2") (pintype "passive"))
      (node (ref "C23") (pin "2") (pinfunction "2_2") (pintype "passive"))
      (node (ref "C6") (pin "2") (pinfunction "2_2") (pintype "passive"))
      (node (ref "C8") (pin "1") (pinfunction "1_1") (pintype "passive"))
      (node (ref "D4") (pin "2") (pinfunction "K_2") (pintype "passive"))
      (node (ref "P13") (pin "7") (pinfunction "7_7") (pintype "passive"))
      (node (ref "P13") (pin "8") (pinfunction "8_8") (pintype "passive"))
      (node (ref "R1") (pin "1") (pintype "passive"))
      (node (ref "R4") (pin "1") (pintype "passive"))
      (node (ref "R6") (pin "2") (pinfunction "2_2") (pintype "passive"))
      (node (ref "U2") (pin "18") (pinfunction "VDD_18") (pintype "power_in"))
      (node (ref "U2") (pin "35") (pinfunction "VDD_35") (pintype "power_in"))
      (node (ref "U2") (pin "51") (pinfunction "VDD_51") (pintype "power_in"))
      (node (ref "U2") (pin "68") (pinfunction "VDD_68") (pintype "power_in"))
    )
    (net (code "94") (name "unconnected-(P3-RFU1-PadA8)") (class "Default")
      (node (ref "P3") (pin "A8") (pinfunction "RFU1_A8") (pintype "bidirectional+no_connect"))
    )
    (net (code "95") (name "unconnected-(P3-RFU1-PadB8)") (class "Default")
      (node (ref "P3") (pin "B8") (pinfunction "RFU1_B8") (pintype "bidirectional+no_connect"))
    )
    (net (code "96") (name "unconnected-(P5-RFU1-PadA8)") (class "Default")
      (node (ref "P5") (pin "A8") (pinfunction "RFU1_A8") (pintype "bidirectional+no_connect"))
    )
    (net (code "97") (name "unconnected-(P5-RFU1-PadB8)") (class "Default")
      (node (ref "P5") (pin "B8") (pinfunction "RFU1_B8") (pintype "bidirectional+no_connect"))
    )
    (net (code "98") (name "unconnected-(P10-Pad7)") (class "Default")
      (node (ref "P10") (pin "7") (pintype "passive"))
    )
    (net (code "99") (name "unconnected-(S1-NO-Pad3)") (class "Default")
      (node (ref "S1") (pin "3") (pinfunction "NO_3") (pintype "passive"))
    )
    (net (code "100") (name "unconnected-(U1-NC.-Pad1)") (class "Default")
      (node (ref "U1") (pin "1") (pinfunction "NC._1") (pintype "passive"))
    )
  )
)
